# TSOC_GROVEY_WIFI_R0_2.net
KiCad netlist of a schematic drawn in EAGLE
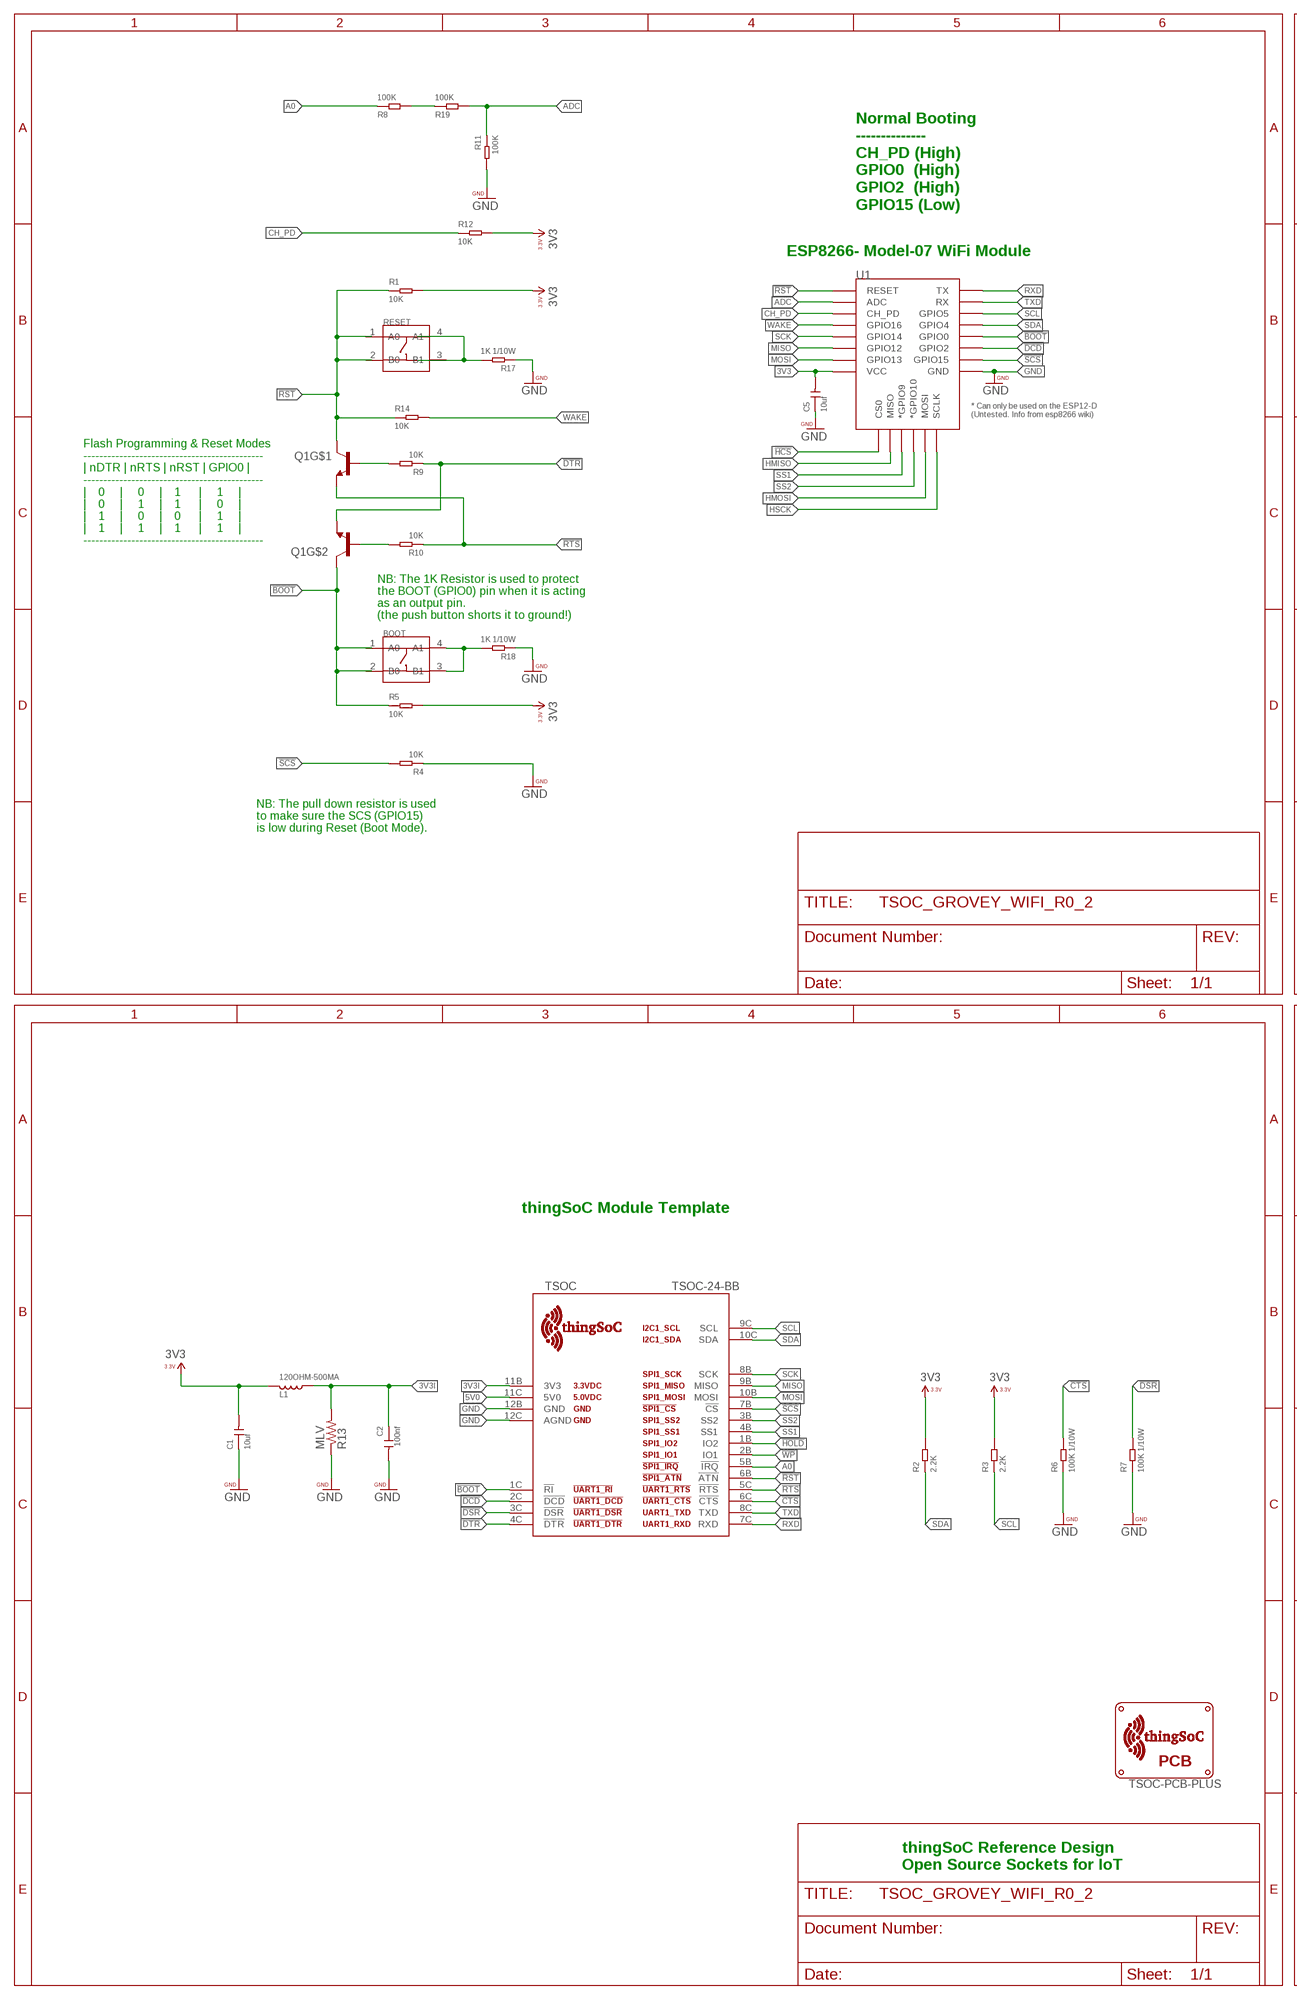
[diagram p0: schematic, sheet 1, part 1 of 2]
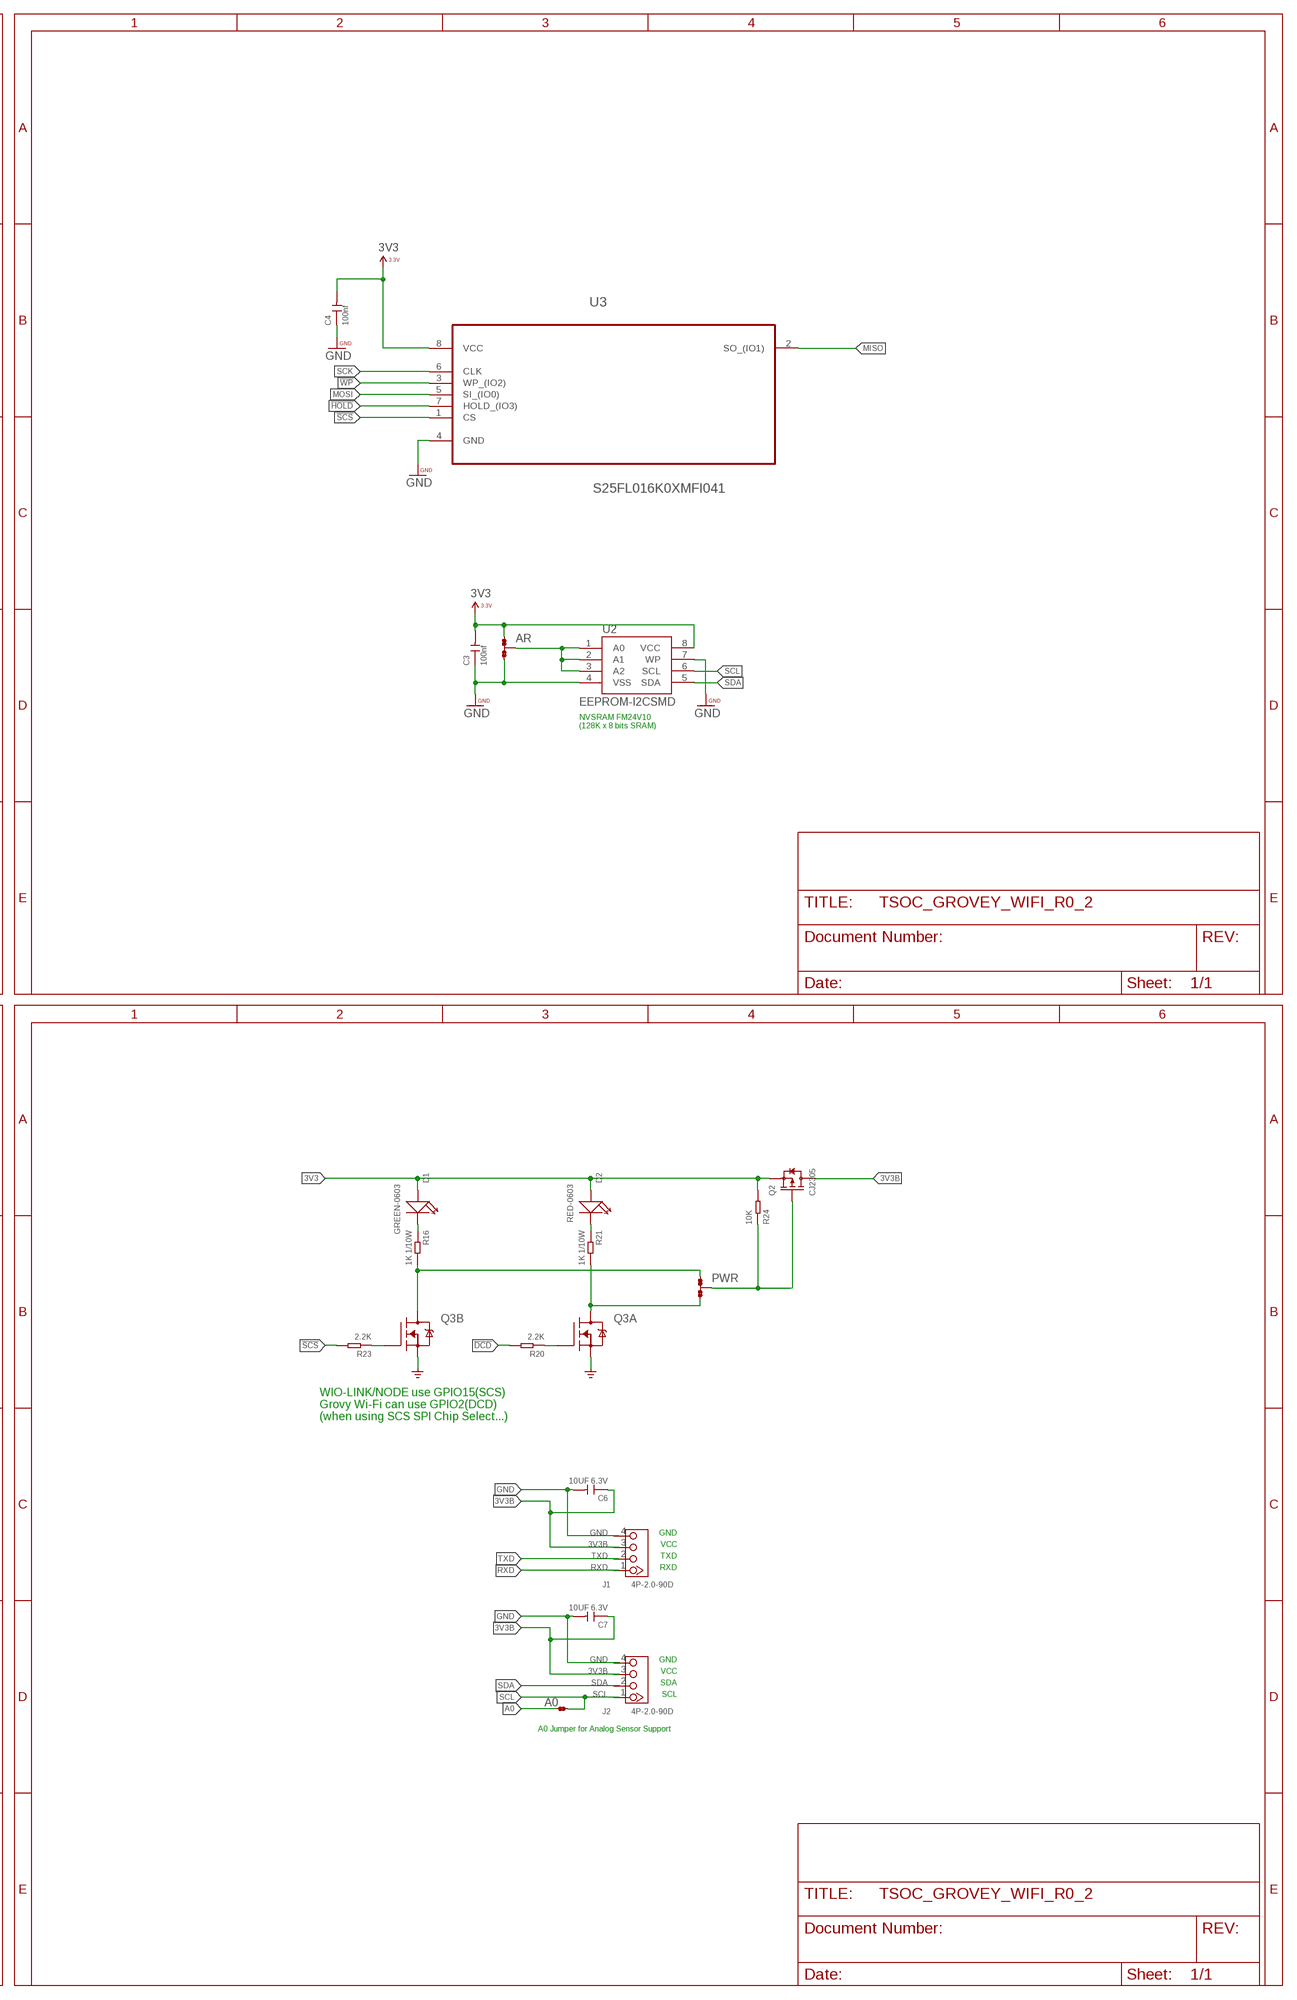
[diagram p1: schematic, sheet 1, part 2 of 2]

(export (version "E")
  (design (tool "Eeschema 10.0.6"))
  (components
    (comp (ref "A0")
      (value "JMP-2-NO")
      (footprint "eagle-import:JMP-2-NO")
      (libsource (lib "eagle-import") (part "JMP-2-NO"))
    )
    (comp (ref "AR")
      (value "JMP-3-1_2")
      (footprint "eagle-import:JMP-3-1_2")
      (libsource (lib "eagle-import") (part "JMP-3-1_2"))
    )
    (comp (ref "BOOT")
      (value "SMD-SWITCH-TACTILE-SPST-NO(4P-D6.0MM)")
      (footprint "eagle-import:SW4-SMD-6.0X6.0X5.0MM")
      (fields (field (name "MPN") "DTSM-62K-S-V-T/R(SN431)"))
      (libsource (lib "eagle-import") (part "SMD-SWITCH-TACTILE-SPST-NO(4P-D6.0MM)"))
    )
    (comp (ref "C1")
      (value "10uf")
      (footprint "eagle-import:C1206")
      (fields (field (name "MPN") "CC1206KKX5R8BB106"))
      (libsource (lib "eagle-import") (part "CERAMIC-10UF-25V-10%-X5R(1206)"))
    )
    (comp (ref "C2")
      (value "100nf")
      (footprint "eagle-import:C0603")
      (fields (field (name "MPN") "CC0603KRX7R9BB104"))
      (libsource (lib "eagle-import") (part "CERAMIC-100NF-50V-10%-X7R(0603)"))
    )
    (comp (ref "C3")
      (value "100nf")
      (footprint "eagle-import:C0603")
      (fields (field (name "MPN") "CC0603KRX7R9BB104"))
      (libsource (lib "eagle-import") (part "CERAMIC-100NF-50V-10%-X7R(0603)"))
    )
    (comp (ref "C4")
      (value "100nf")
      (footprint "eagle-import:C0603")
      (fields (field (name "MPN") "CC0603KRX7R9BB104"))
      (libsource (lib "eagle-import") (part "CERAMIC-100NF-50V-10%-X7R(0603)"))
    )
    (comp (ref "C5")
      (value "10uf")
      (footprint "eagle-import:C1206")
      (fields (field (name "MPN") "CC1206KKX5R8BB106"))
      (libsource (lib "eagle-import") (part "CERAMIC-10UF-25V-10%-X5R(1206)"))
    )
    (comp (ref "C6")
      (value "10UF 6.3V")
      (footprint "eagle-import:C0603")
      (fields (field (name "MPN") "CC0603MRX5R5BB106"))
      (libsource (lib "eagle-import") (part "CERAMIC-10UF-6.3V-20%-X5R(0603)"))
    )
    (comp (ref "C7")
      (value "10UF 6.3V")
      (footprint "eagle-import:C0603")
      (fields (field (name "MPN") "CC0603MRX5R5BB106"))
      (libsource (lib "eagle-import") (part "CERAMIC-10UF-6.3V-20%-X5R(0603)"))
    )
    (comp (ref "D1")
      (value "GREEN-0603")
      (footprint "eagle-import:LED-0603")
      (fields (field (name "MPN") "19-217-G7C-AN1P2-3T"))
      (libsource (lib "eagle-import") (part "SMD-LED-CLEAR-GREEN(0603)"))
    )
    (comp (ref "D2")
      (value "RED-0603")
      (footprint "eagle-import:LED-0603")
      (fields (field (name "MPN") "19-217-R6C-AL1M2VY-3T"))
      (libsource (lib "eagle-import") (part "LED-SMD-RED-DIFFUSED(0603)"))
    )
    (comp (ref "J1")
      (value "4P-2.0-90D")
      (footprint "eagle-import:HW4-2.0-90D")
      (libsource (lib "eagle-import") (part "GROVE-CONNECTOR-DIP-90D(4P-2.0)"))
    )
    (comp (ref "J2")
      (value "4P-2.0-90D")
      (footprint "eagle-import:HW4-2.0-90D")
      (libsource (lib "eagle-import") (part "GROVE-CONNECTOR-DIP-90D(4P-2.0)"))
    )
    (comp (ref "L1")
      (value "120OHM-500MA")
      (footprint "eagle-import:L0603")
      (fields (field (name "MPN") "BLM18AG121SN1D"))
      (libsource (lib "eagle-import") (part "SMD-FERRITE-CHIP-120-OHM-500MA(0603)"))
    )
    (comp (ref "PCB")
      (value "TSOC-PCB-PLUS")
      (footprint "eagle-import:TSOC-BB-BRD-PLUS-DIM")
      (libsource (lib "eagle-import") (part "TSOC-PCB-PLUS"))
    )
    (comp (ref "PWR")
      (value "JMP-3-1_2")
      (footprint "eagle-import:JMP-3-1_2")
      (libsource (lib "eagle-import") (part "JMP-3-1_2"))
    )
    (comp (ref "Q1")
      (value "MMBT2222A")
      (footprint "eagle-import:SOT363")
      (libsource (lib "eagle-import") (part "MMDT3904"))
    )
    (comp (ref "Q2")
      (value "CJ2305")
      (footprint "eagle-import:SOT-23")
      (libsource (lib "eagle-import") (part "MOSFET-P'SI2323CDS/SI2305DS{lt}BR{gt}'"))
    )
    (comp (ref "Q3")
      (value "FDG1024NZ")
      (footprint "eagle-import:SOT95P280X110-6N")
      (libsource (lib "eagle-import") (part "FDG1024NZ"))
    )
    (comp (ref "R1")
      (value "10K")
      (footprint "eagle-import:R0603")
      (fields (field (name "MPN") "RC0603FR-0710KL"))
      (libsource (lib "eagle-import") (part "SMD-RES-10K-1%-1/10W(0603)"))
    )
    (comp (ref "R2")
      (value "2.2K")
      (footprint "eagle-import:R0603")
      (fields (field (name "MPN") "RC0603JR-072K2L"))
      (libsource (lib "eagle-import") (part "SMD-RES-2.2K-5%-1/10W(0603)"))
    )
    (comp (ref "R3")
      (value "2.2K")
      (footprint "eagle-import:R0603")
      (fields (field (name "MPN") "RC0603JR-072K2L"))
      (libsource (lib "eagle-import") (part "SMD-RES-2.2K-5%-1/10W(0603)"))
    )
    (comp (ref "R4")
      (value "10K")
      (footprint "eagle-import:R0603")
      (fields (field (name "MPN") "RC0603FR-0710KL"))
      (libsource (lib "eagle-import") (part "SMD-RES-10K-1%-1/10W(0603)"))
    )
    (comp (ref "R5")
      (value "10K")
      (footprint "eagle-import:R0603")
      (fields (field (name "MPN") "RC0603FR-0710KL"))
      (libsource (lib "eagle-import") (part "SMD-RES-10K-1%-1/10W(0603)"))
    )
    (comp (ref "R6")
      (value "100K 1/10W")
      (footprint "eagle-import:R0603")
      (fields (field (name "MPN") "RC0603JR-07100KL"))
      (libsource (lib "eagle-import") (part "SMD-RES-100K-5%-1/10W(0603)"))
    )
    (comp (ref "R7")
      (value "100K 1/10W")
      (footprint "eagle-import:R0603")
      (fields (field (name "MPN") "RC0603JR-07100KL"))
      (libsource (lib "eagle-import") (part "SMD-RES-100K-5%-1/10W(0603)"))
    )
    (comp (ref "R8")
      (value "100K")
      (footprint "eagle-import:R0603")
      (fields (field (name "MPN") "RC0603FR-07100KL"))
      (libsource (lib "eagle-import") (part "SMD-RES-100K-1%-1/10W(0603)"))
    )
    (comp (ref "R9")
      (value "10K")
      (footprint "eagle-import:R0603")
      (fields (field (name "MPN") "RC0603FR-0710KL"))
      (libsource (lib "eagle-import") (part "SMD-RES-10K-1%-1/10W(0603)"))
    )
    (comp (ref "R10")
      (value "10K")
      (footprint "eagle-import:R0603")
      (fields (field (name "MPN") "RC0603FR-0710KL"))
      (libsource (lib "eagle-import") (part "SMD-RES-10K-1%-1/10W(0603)"))
    )
    (comp (ref "R11")
      (value "100K")
      (footprint "eagle-import:R0603")
      (fields (field (name "MPN") "RC0603FR-07100KL"))
      (libsource (lib "eagle-import") (part "SMD-RES-100K-1%-1/10W(0603)"))
    )
    (comp (ref "R12")
      (value "10K")
      (footprint "eagle-import:R0603")
      (fields (field (name "MPN") "RC0603FR-0710KL"))
      (libsource (lib "eagle-import") (part "SMD-RES-10K-1%-1/10W(0603)"))
    )
    (comp (ref "R13")
      (value "MLV")
      (footprint "eagle-import:0402-RES")
      (libsource (lib "eagle-import") (part "RESISTOR0402"))
    )
    (comp (ref "R14")
      (value "10K")
      (footprint "eagle-import:R0603")
      (fields (field (name "MPN") "RC0603FR-0710KL"))
      (libsource (lib "eagle-import") (part "SMD-RES-10K-1%-1/10W(0603)"))
    )
    (comp (ref "R16")
      (value "1K 1/10W")
      (footprint "eagle-import:R0603")
      (fields (field (name "MPN") "RC0603JR-071KL"))
      (libsource (lib "eagle-import") (part "SMD-RES-1K-5%-1/10W(0603)"))
    )
    (comp (ref "R17")
      (value "1K 1/10W")
      (footprint "eagle-import:R0603")
      (fields (field (name "MPN") "RC0603JR-071KL"))
      (libsource (lib "eagle-import") (part "SMD-RES-1K-5%-1/10W(0603)"))
    )
    (comp (ref "R18")
      (value "1K 1/10W")
      (footprint "eagle-import:R0603")
      (fields (field (name "MPN") "RC0603JR-071KL"))
      (libsource (lib "eagle-import") (part "SMD-RES-1K-5%-1/10W(0603)"))
    )
    (comp (ref "R19")
      (value "100K")
      (footprint "eagle-import:R0603")
      (fields (field (name "MPN") "RC0603FR-07100KL"))
      (libsource (lib "eagle-import") (part "SMD-RES-100K-1%-1/10W(0603)"))
    )
    (comp (ref "R20")
      (value "2.2K")
      (footprint "eagle-import:R0603")
      (fields (field (name "MPN") "RC0603JR-072K2L"))
      (libsource (lib "eagle-import") (part "SMD-RES-2.2K-5%-1/10W(0603)"))
    )
    (comp (ref "R21")
      (value "1K 1/10W")
      (footprint "eagle-import:R0603")
      (fields (field (name "MPN") "RC0603JR-071KL"))
      (libsource (lib "eagle-import") (part "SMD-RES-1K-5%-1/10W(0603)"))
    )
    (comp (ref "R23")
      (value "2.2K")
      (footprint "eagle-import:R0603")
      (fields (field (name "MPN") "RC0603JR-072K2L"))
      (libsource (lib "eagle-import") (part "SMD-RES-2.2K-5%-1/10W(0603)"))
    )
    (comp (ref "R24")
      (value "10K")
      (footprint "eagle-import:R0603")
      (fields (field (name "MPN") "RC0603FR-0710KL"))
      (libsource (lib "eagle-import") (part "SMD-RES-10K-1%-1/10W(0603)"))
    )
    (comp (ref "RESET")
      (value "SMD-SWITCH-TACTILE-SPST-NO(4P-D6.0MM)")
      (footprint "eagle-import:SW4-SMD-6.0X6.0X5.0MM")
      (fields (field (name "MPN") "DTSM-62K-S-V-T/R(SN431)"))
      (libsource (lib "eagle-import") (part "SMD-SWITCH-TACTILE-SPST-NO(4P-D6.0MM)"))
    )
    (comp (ref "TSOC")
      (value "TSOC-24-BB")
      (footprint "eagle-import:TSOC-BB-S24")
      (libsource (lib "eagle-import") (part "TSOC-24-BB"))
    )
    (comp (ref "U1")
      (value "ESP12ESMD")
      (footprint "eagle-import:ESP12E-SMD")
      (libsource (lib "eagle-import") (part "ESP12ESMD"))
    )
    (comp (ref "U2")
      (value "EEPROM-I2CSMD")
      (footprint "eagle-import:SO08")
      (libsource (lib "eagle-import") (part "EEPROM-I2CSMD"))
    )
    (comp (ref "U3")
      (value "S25FL016K0XMFI041")
      (footprint "eagle-import:SOIC127P600X175-8N")
      (libsource (lib "eagle-import") (part "S25FL016K0XMFI041"))
    )
  )
  (nets
    (net (code "1") (name "/~{BOOT}") (class "Default")
      (node (ref "BOOT") (pin "1") (pinfunction "A0_1") (pintype "bidirectional"))
      (node (ref "BOOT") (pin "2") (pinfunction "B0_2") (pintype "bidirectional"))
      (node (ref "Q1") (pin "6") (pinfunction "C_6") (pintype "passive"))
      (node (ref "R5") (pin "1") (pinfunction "1_1") (pintype "passive"))
      (node (ref "TSOC") (pin "1C") (pinfunction "~{RI}_1C") (pintype "bidirectional"))
      (node (ref "U1") (pin "GPIO0") (pinfunction "GPIO0_GPIO0") (pintype "bidirectional"))
    )
    (net (code "2") (name "/~{CTS}") (class "Default")
      (node (ref "R6") (pin "2") (pinfunction "2_2") (pintype "passive"))
      (node (ref "TSOC") (pin "6C") (pinfunction "~{CTS}_6C") (pintype "bidirectional"))
    )
    (net (code "3") (name "/~{DCD}") (class "Default")
      (node (ref "R20") (pin "2") (pinfunction "2_2") (pintype "passive"))
      (node (ref "TSOC") (pin "2C") (pinfunction "~{DCD}_2C") (pintype "bidirectional"))
      (node (ref "U1") (pin "GPIO2") (pinfunction "GPIO2_GPIO2") (pintype "bidirectional"))
    )
    (net (code "4") (name "/~{DSR}") (class "Default")
      (node (ref "R7") (pin "2") (pinfunction "2_2") (pintype "passive"))
      (node (ref "TSOC") (pin "3C") (pinfunction "~{DSR}_3C") (pintype "bidirectional"))
    )
    (net (code "5") (name "/~{DTR}") (class "Default")
      (node (ref "Q1") (pin "1") (pinfunction "E_1") (pintype "passive"))
      (node (ref "R9") (pin "1") (pinfunction "1_1") (pintype "passive"))
      (node (ref "TSOC") (pin "4C") (pinfunction "~{DTR}_4C") (pintype "bidirectional"))
    )
    (net (code "6") (name "/~{HCS}") (class "Default")
      (node (ref "U1") (pin "CS0") (pinfunction "CS0_CS0") (pintype "bidirectional"))
    )
    (net (code "7") (name "/~{HOLD}") (class "Default")
      (node (ref "TSOC") (pin "1B") (pinfunction "IO2_1B") (pintype "bidirectional"))
      (node (ref "U3") (pin "7") (pinfunction "HOLD_(IO3)_7") (pintype "bidirectional"))
    )
    (net (code "8") (name "/~{RST}") (class "Default")
      (node (ref "Q1") (pin "3") (pinfunction "C_3") (pintype "passive"))
      (node (ref "R1") (pin "1") (pinfunction "1_1") (pintype "passive"))
      (node (ref "R14") (pin "1") (pinfunction "1_1") (pintype "passive"))
      (node (ref "RESET") (pin "1") (pinfunction "A0_1") (pintype "bidirectional"))
      (node (ref "RESET") (pin "2") (pinfunction "B0_2") (pintype "bidirectional"))
      (node (ref "TSOC") (pin "6B") (pinfunction "~{ATN}_6B") (pintype "bidirectional"))
      (node (ref "U1") (pin "RESET") (pinfunction "RESET_RESET") (pintype "bidirectional"))
    )
    (net (code "9") (name "/~{RTS}") (class "Default")
      (node (ref "Q1") (pin "4") (pinfunction "E_4") (pintype "passive"))
      (node (ref "R10") (pin "1") (pinfunction "1_1") (pintype "passive"))
      (node (ref "TSOC") (pin "5C") (pinfunction "~{RTS}_5C") (pintype "bidirectional"))
    )
    (net (code "10") (name "/~{SCS}") (class "Default")
      (node (ref "R23") (pin "2") (pinfunction "2_2") (pintype "passive"))
      (node (ref "R4") (pin "2") (pinfunction "2_2") (pintype "passive"))
      (node (ref "TSOC") (pin "7B") (pinfunction "~{CS}_7B") (pintype "bidirectional"))
      (node (ref "U1") (pin "GPIO15") (pinfunction "GPIO15_GPIO15") (pintype "bidirectional"))
      (node (ref "U3") (pin "1") (pinfunction "CS_1") (pintype "input"))
    )
    (net (code "11") (name "/~{WP}") (class "Default")
      (node (ref "TSOC") (pin "2B") (pinfunction "IO1_2B") (pintype "bidirectional"))
      (node (ref "U3") (pin "3") (pinfunction "WP_(IO2)_3") (pintype "bidirectional"))
    )
    (net (code "12") (name "3V3") (class "Default")
      (node (ref "AR") (pin "1") (pinfunction "1_1") (pintype "passive"))
      (node (ref "C1") (pin "2") (pinfunction "2_2") (pintype "passive"))
      (node (ref "C3") (pin "2") (pinfunction "2_2") (pintype "passive"))
      (node (ref "C4") (pin "2") (pinfunction "2_2") (pintype "passive"))
      (node (ref "C5") (pin "2") (pinfunction "2_2") (pintype "passive"))
      (node (ref "D1") (pin "+") (pinfunction "+_+") (pintype "passive"))
      (node (ref "D2") (pin "+") (pinfunction "+_+") (pintype "passive"))
      (node (ref "L1") (pin "1") (pinfunction "1_1") (pintype "passive"))
      (node (ref "Q2") (pin "2") (pinfunction "S_2") (pintype "passive"))
      (node (ref "R1") (pin "2") (pinfunction "2_2") (pintype "passive"))
      (node (ref "R12") (pin "2") (pinfunction "2_2") (pintype "passive"))
      (node (ref "R2") (pin "2") (pinfunction "2_2") (pintype "passive"))
      (node (ref "R24") (pin "2") (pinfunction "2_2") (pintype "passive"))
      (node (ref "R3") (pin "2") (pinfunction "2_2") (pintype "passive"))
      (node (ref "R5") (pin "2") (pinfunction "2_2") (pintype "passive"))
      (node (ref "U1") (pin "VCC") (pinfunction "VCC_VCC") (pintype "bidirectional"))
      (node (ref "U2") (pin "8") (pinfunction "VCC_8") (pintype "power_in"))
      (node (ref "U3") (pin "8") (pinfunction "VCC_8") (pintype "power_in"))
    )
    (net (code "13") (name "3V3B") (class "Default")
      (node (ref "C6") (pin "1") (pinfunction "1_1") (pintype "passive"))
      (node (ref "C7") (pin "1") (pinfunction "1_1") (pintype "passive"))
      (node (ref "J1") (pin "3") (pinfunction "3_3") (pintype "bidirectional"))
      (node (ref "J2") (pin "3") (pinfunction "3_3") (pintype "bidirectional"))
      (node (ref "Q2") (pin "3") (pinfunction "D_3") (pintype "passive"))
    )
    (net (code "14") (name "3V3I") (class "Default")
      (node (ref "C2") (pin "1") (pinfunction "1_1") (pintype "passive"))
      (node (ref "L1") (pin "2") (pinfunction "2_2") (pintype "passive"))
      (node (ref "R13") (pin "2") (pinfunction "2_2") (pintype "passive"))
      (node (ref "TSOC") (pin "11B") (pinfunction "3V3_11B") (pintype "bidirectional"))
    )
    (net (code "15") (name "5V0") (class "Default")
      (node (ref "TSOC") (pin "11C") (pinfunction "5V0_11C") (pintype "bidirectional"))
    )
    (net (code "16") (name "A0") (class "Default")
      (node (ref "A0") (pin "2") (pinfunction "2_2") (pintype "passive"))
      (node (ref "R8") (pin "1") (pinfunction "1_1") (pintype "passive"))
      (node (ref "TSOC") (pin "5B") (pinfunction "~{IRQ}_5B") (pintype "bidirectional"))
    )
    (net (code "17") (name "ADC") (class "Default")
      (node (ref "R11") (pin "1") (pinfunction "1_1") (pintype "passive"))
      (node (ref "R19") (pin "2") (pinfunction "2_2") (pintype "passive"))
      (node (ref "U1") (pin "ADC") (pinfunction "ADC_ADC") (pintype "bidirectional"))
    )
    (net (code "18") (name "CH_PD") (class "Default")
      (node (ref "R12") (pin "1") (pinfunction "1_1") (pintype "passive"))
      (node (ref "U1") (pin "CH_PD") (pinfunction "CH_PD_CH_PD") (pintype "bidirectional"))
    )
    (net (code "19") (name "GND") (class "Default")
      (node (ref "AR") (pin "3") (pinfunction "3_3") (pintype "passive"))
      (node (ref "C1") (pin "1") (pinfunction "1_1") (pintype "passive"))
      (node (ref "C2") (pin "2") (pinfunction "2_2") (pintype "passive"))
      (node (ref "C3") (pin "1") (pinfunction "1_1") (pintype "passive"))
      (node (ref "C4") (pin "1") (pinfunction "1_1") (pintype "passive"))
      (node (ref "C5") (pin "1") (pinfunction "1_1") (pintype "passive"))
      (node (ref "C6") (pin "2") (pinfunction "2_2") (pintype "passive"))
      (node (ref "C7") (pin "2") (pinfunction "2_2") (pintype "passive"))
      (node (ref "J1") (pin "4") (pinfunction "4_4") (pintype "bidirectional"))
      (node (ref "J2") (pin "4") (pinfunction "4_4") (pintype "bidirectional"))
      (node (ref "Q3") (pin "1") (pinfunction "S_1") (pintype "passive"))
      (node (ref "Q3") (pin "4") (pinfunction "S_4") (pintype "passive"))
      (node (ref "R11") (pin "2") (pinfunction "2_2") (pintype "passive"))
      (node (ref "R13") (pin "1") (pinfunction "1_1") (pintype "passive"))
      (node (ref "R17") (pin "1") (pinfunction "1_1") (pintype "passive"))
      (node (ref "R18") (pin "1") (pinfunction "1_1") (pintype "passive"))
      (node (ref "R4") (pin "1") (pinfunction "1_1") (pintype "passive"))
      (node (ref "R6") (pin "1") (pinfunction "1_1") (pintype "passive"))
      (node (ref "R7") (pin "1") (pinfunction "1_1") (pintype "passive"))
      (node (ref "TSOC") (pin "12B") (pinfunction "GND_12B") (pintype "bidirectional"))
      (node (ref "TSOC") (pin "12C") (pinfunction "AGND_12C") (pintype "bidirectional"))
      (node (ref "U1") (pin "GND") (pinfunction "GND_GND") (pintype "bidirectional"))
      (node (ref "U2") (pin "4") (pinfunction "VSS_4") (pintype "power_in"))
      (node (ref "U2") (pin "7") (pinfunction "WP_7") (pintype "bidirectional"))
      (node (ref "U3") (pin "4") (pinfunction "GND_4") (pintype "passive"))
    )
    (net (code "20") (name "HMISO") (class "Default")
      (node (ref "U1") (pin "MISO") (pinfunction "MISO_MISO") (pintype "bidirectional"))
    )
    (net (code "21") (name "HMOSI") (class "Default")
      (node (ref "U1") (pin "MOSI") (pinfunction "MOSI_MOSI") (pintype "bidirectional"))
    )
    (net (code "22") (name "HSCK") (class "Default")
      (node (ref "U1") (pin "SCLK") (pinfunction "SCLK_SCLK") (pintype "bidirectional"))
    )
    (net (code "23") (name "MISO") (class "Default")
      (node (ref "TSOC") (pin "9B") (pinfunction "MISO_9B") (pintype "bidirectional"))
      (node (ref "U1") (pin "GPIO12") (pinfunction "GPIO12_GPIO12") (pintype "bidirectional"))
      (node (ref "U3") (pin "2") (pinfunction "SO_(IO1)_2") (pintype "output"))
    )
    (net (code "24") (name "MOSI") (class "Default")
      (node (ref "TSOC") (pin "10B") (pinfunction "MOSI_10B") (pintype "bidirectional"))
      (node (ref "U1") (pin "GPIO13") (pinfunction "GPIO13_GPIO13") (pintype "bidirectional"))
      (node (ref "U3") (pin "5") (pinfunction "SI_(IO0)_5") (pintype "bidirectional"))
    )
    (net (code "25") (name "Net-(BOOT-A1)") (class "Default")
      (node (ref "BOOT") (pin "3") (pinfunction "B1_3") (pintype "bidirectional"))
      (node (ref "BOOT") (pin "4") (pinfunction "A1_4") (pintype "bidirectional"))
      (node (ref "R18") (pin "2") (pinfunction "2_2") (pintype "passive"))
    )
    (net (code "26") (name "Net-(D1-Pad-)") (class "Default")
      (node (ref "D1") (pin "-") (pinfunction "-_-") (pintype "passive"))
      (node (ref "R16") (pin "1") (pinfunction "1_1") (pintype "passive"))
    )
    (net (code "27") (name "Net-(D2-Pad-)") (class "Default")
      (node (ref "D2") (pin "-") (pinfunction "-_-") (pintype "passive"))
      (node (ref "R21") (pin "1") (pinfunction "1_1") (pintype "passive"))
    )
    (net (code "28") (name "Net-(Q1A-B)") (class "Default")
      (node (ref "Q1") (pin "5") (pinfunction "B_5") (pintype "passive"))
      (node (ref "R9") (pin "2") (pinfunction "2_2") (pintype "passive"))
    )
    (net (code "29") (name "Net-(Q1B-B)") (class "Default")
      (node (ref "Q1") (pin "2") (pinfunction "B_2") (pintype "passive"))
      (node (ref "R10") (pin "2") (pinfunction "2_2") (pintype "passive"))
    )
    (net (code "30") (name "Net-(Q2-G)") (class "Default")
      (node (ref "PWR") (pin "2") (pinfunction "2_2") (pintype "passive"))
      (node (ref "Q2") (pin "1") (pinfunction "G_1") (pintype "passive"))
      (node (ref "R24") (pin "1") (pinfunction "1_1") (pintype "passive"))
    )
    (net (code "31") (name "Net-(Q3A-D)") (class "Default")
      (node (ref "PWR") (pin "3") (pinfunction "3_3") (pintype "passive"))
      (node (ref "Q3") (pin "6") (pinfunction "D_6") (pintype "passive"))
      (node (ref "R21") (pin "2") (pinfunction "2_2") (pintype "passive"))
    )
    (net (code "32") (name "Net-(Q3A-G)") (class "Default")
      (node (ref "Q3") (pin "2") (pinfunction "G_2") (pintype "passive"))
      (node (ref "R20") (pin "1") (pinfunction "1_1") (pintype "passive"))
    )
    (net (code "33") (name "Net-(Q3B-D)") (class "Default")
      (node (ref "PWR") (pin "1") (pinfunction "1_1") (pintype "passive"))
      (node (ref "Q3") (pin "3") (pinfunction "D_3") (pintype "passive"))
      (node (ref "R16") (pin "2") (pinfunction "2_2") (pintype "passive"))
    )
    (net (code "34") (name "Net-(Q3B-G)") (class "Default")
      (node (ref "Q3") (pin "5") (pinfunction "G_5") (pintype "passive"))
      (node (ref "R23") (pin "1") (pinfunction "1_1") (pintype "passive"))
    )
    (net (code "35") (name "Net-(R19-Pad1)") (class "Default")
      (node (ref "R19") (pin "1") (pinfunction "1_1") (pintype "passive"))
      (node (ref "R8") (pin "2") (pinfunction "2_2") (pintype "passive"))
    )
    (net (code "36") (name "Net-(RESET-A1)") (class "Default")
      (node (ref "R17") (pin "2") (pinfunction "2_2") (pintype "passive"))
      (node (ref "RESET") (pin "3") (pinfunction "B1_3") (pintype "bidirectional"))
      (node (ref "RESET") (pin "4") (pinfunction "A1_4") (pintype "bidirectional"))
    )
    (net (code "37") (name "Net-(U2-A0)") (class "Default")
      (node (ref "AR") (pin "2") (pinfunction "2_2") (pintype "passive"))
      (node (ref "U2") (pin "1") (pinfunction "A0_1") (pintype "bidirectional"))
      (node (ref "U2") (pin "2") (pinfunction "A1_2") (pintype "bidirectional"))
      (node (ref "U2") (pin "3") (pinfunction "A2_3") (pintype "bidirectional"))
    )
    (net (code "38") (name "RXD") (class "Default")
      (node (ref "J1") (pin "1") (pinfunction "1_1") (pintype "bidirectional"))
      (node (ref "TSOC") (pin "7C") (pinfunction "RXD_7C") (pintype "bidirectional"))
      (node (ref "U1") (pin "TXD0") (pinfunction "TX_TXD0") (pintype "bidirectional"))
    )
    (net (code "39") (name "SCK") (class "Default")
      (node (ref "TSOC") (pin "8B") (pinfunction "SCK_8B") (pintype "bidirectional"))
      (node (ref "U1") (pin "GPIO14") (pinfunction "GPIO14_GPIO14") (pintype "bidirectional"))
      (node (ref "U3") (pin "6") (pinfunction "CLK_6") (pintype "input"))
    )
    (net (code "40") (name "SCL") (class "Default")
      (node (ref "A0") (pin "1") (pinfunction "1_1") (pintype "passive"))
      (node (ref "J2") (pin "1") (pinfunction "1_1") (pintype "bidirectional"))
      (node (ref "R3") (pin "1") (pinfunction "1_1") (pintype "passive"))
      (node (ref "TSOC") (pin "9C") (pinfunction "SCL_9C") (pintype "bidirectional"))
      (node (ref "U1") (pin "GPIO5") (pinfunction "GPIO5_GPIO5") (pintype "bidirectional"))
      (node (ref "U2") (pin "6") (pinfunction "SCL_6") (pintype "bidirectional"))
    )
    (net (code "41") (name "SDA") (class "Default")
      (node (ref "J2") (pin "2") (pinfunction "2_2") (pintype "bidirectional"))
      (node (ref "R2") (pin "1") (pinfunction "1_1") (pintype "passive"))
      (node (ref "TSOC") (pin "10C") (pinfunction "SDA_10C") (pintype "bidirectional"))
      (node (ref "U1") (pin "GPIO4") (pinfunction "GPIO4_GPIO4") (pintype "bidirectional"))
      (node (ref "U2") (pin "5") (pinfunction "SDA_5") (pintype "bidirectional"))
    )
    (net (code "42") (name "SS1") (class "Default")
      (node (ref "TSOC") (pin "4B") (pinfunction "SS1_4B") (pintype "bidirectional"))
      (node (ref "U1") (pin "GPIO9") (pinfunction "*GPIO9_GPIO9") (pintype "bidirectional"))
    )
    (net (code "43") (name "SS2") (class "Default")
      (node (ref "TSOC") (pin "3B") (pinfunction "SS2_3B") (pintype "bidirectional"))
      (node (ref "U1") (pin "GPIO10") (pinfunction "*GPIO10_GPIO10") (pintype "bidirectional"))
    )
    (net (code "44") (name "TXD") (class "Default")
      (node (ref "J1") (pin "2") (pinfunction "2_2") (pintype "bidirectional"))
      (node (ref "TSOC") (pin "8C") (pinfunction "TXD_8C") (pintype "bidirectional"))
      (node (ref "U1") (pin "RXD0") (pinfunction "RX_RXD0") (pintype "bidirectional"))
    )
    (net (code "45") (name "WAKE") (class "Default")
      (node (ref "R14") (pin "2") (pinfunction "2_2") (pintype "passive"))
      (node (ref "U1") (pin "GPIO16") (pinfunction "GPIO16_GPIO16") (pintype "bidirectional"))
    )
  )
)
